# Shematic.net
KiCad netlist of a schematic drawn in Altium Designer
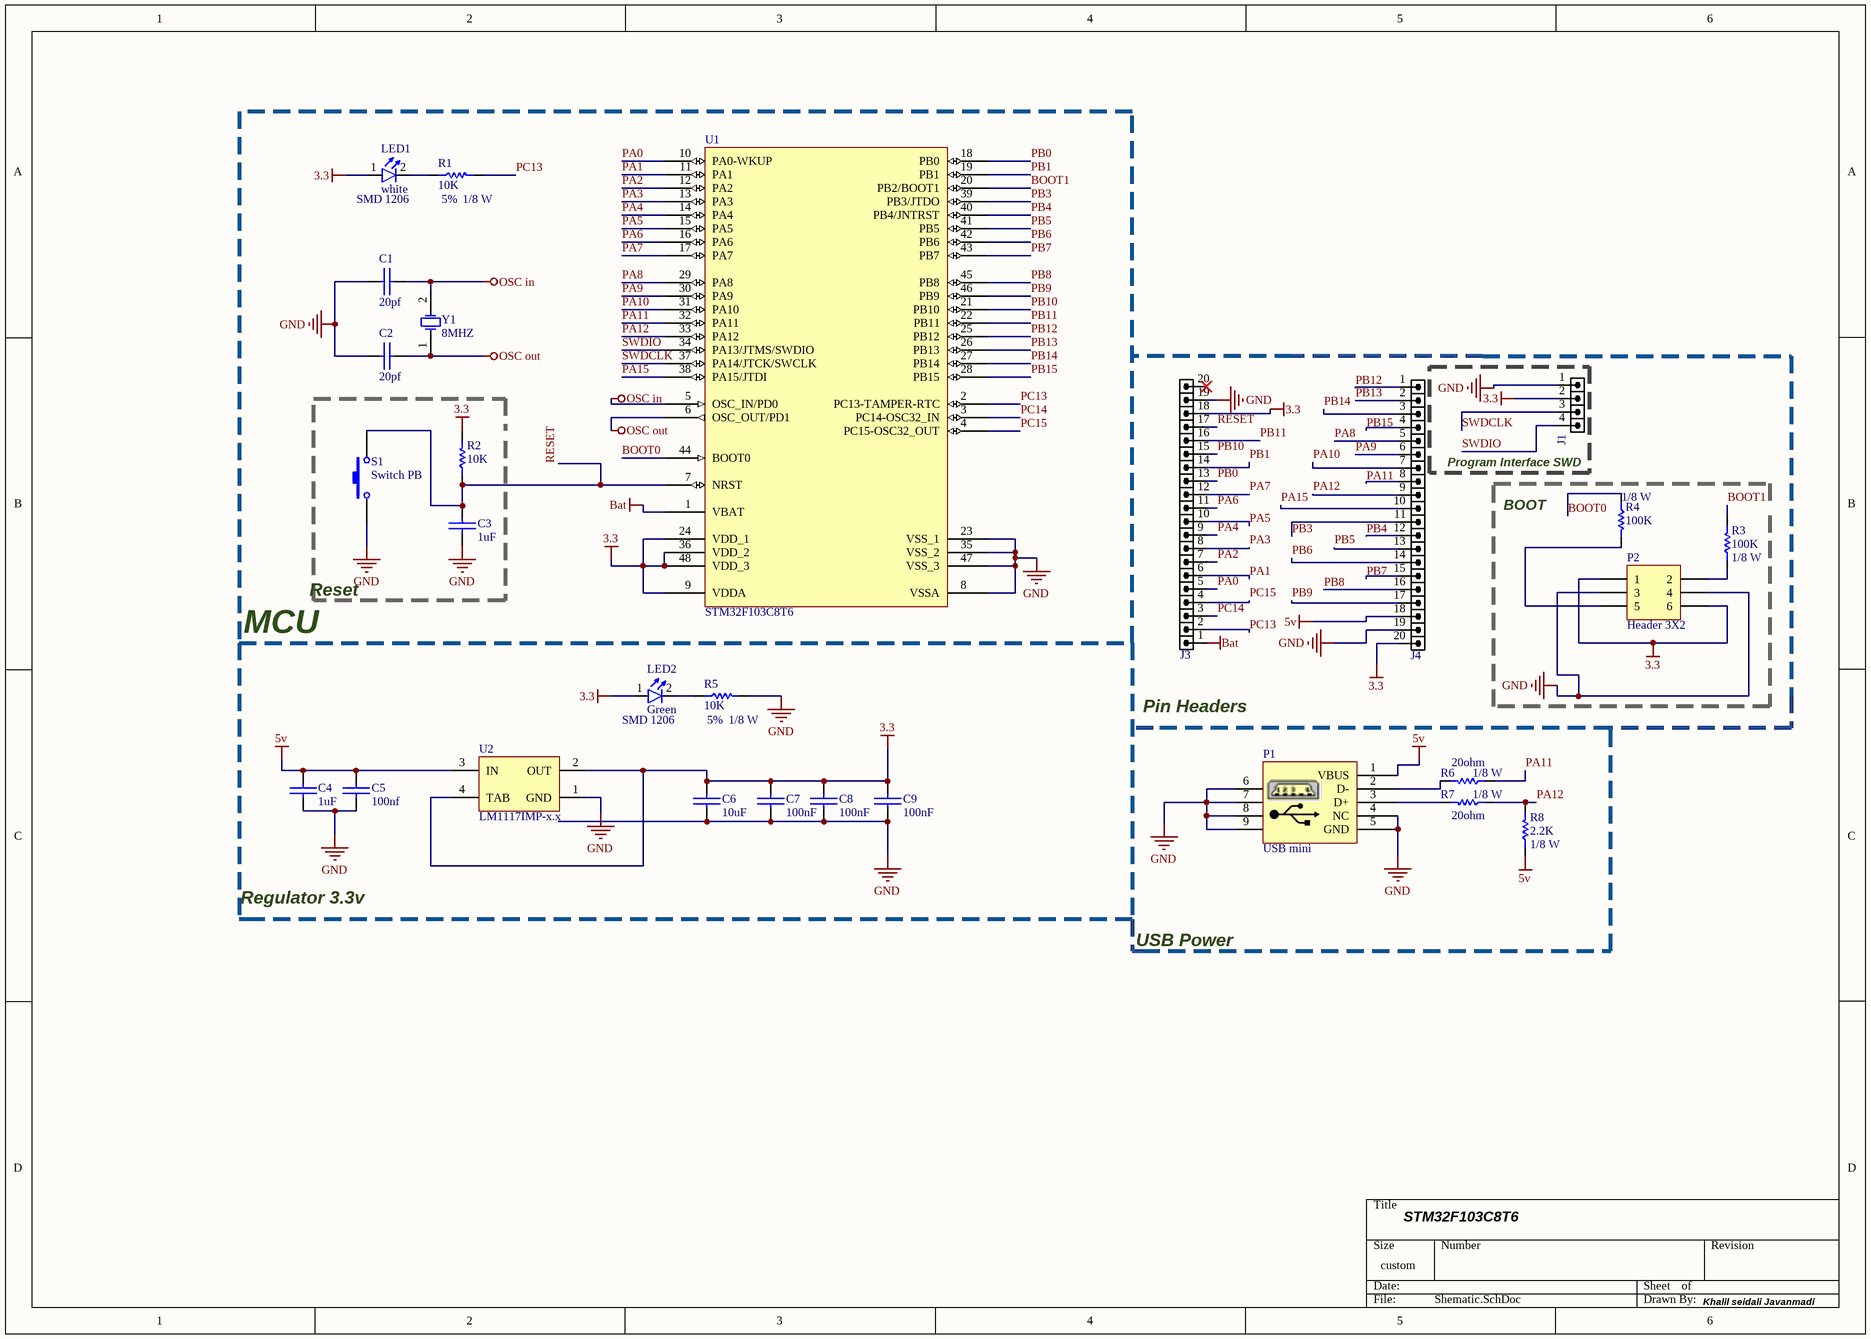
[diagram p0: Shematic.SchDoc]

(export (version "E")
  (design (tool "Eeschema 10.0.6"))
  (components
    (comp (ref "C1")
      (value "20pf")
      (footprint "SMD_CAP_0805")
      (description "Bipolar Capacitor")
      (fields (field (name "VOLTAGE") "100V") (field (name "DESIGNER") "Saeid Jorablo"))
      (libsource (lib "My_Library") (part "Cap-Bipolar"))
    )
    (comp (ref "C2")
      (value "20pf")
      (footprint "SMD_CAP_0805")
      (description "Bipolar Capacitor")
      (fields (field (name "VOLTAGE") "100V") (field (name "DESIGNER") "Saeid Jorablo"))
      (libsource (lib "My_Library") (part "Cap-Bipolar"))
    )
    (comp (ref "C3")
      (value "1uF")
      (footprint "SMD_CAP_0805")
      (description "Bipolar Capacitor")
      (fields (field (name "VOLTAGE") "100V") (field (name "DESIGNER") "Saeid Jorablo"))
      (libsource (lib "My_Library") (part "Cap-Bipolar"))
    )
    (comp (ref "C4")
      (value "1uF")
      (footprint "SMD_CAP_0805")
      (description "Bipolar Capacitor")
      (fields (field (name "VOLTAGE") "100V") (field (name "DESIGNER") "Saeid Jorablo"))
      (libsource (lib "My_Library") (part "Cap-Bipolar"))
    )
    (comp (ref "C5")
      (value "100nf")
      (footprint "SMD_CAP_0805")
      (description "Bipolar Capacitor")
      (fields (field (name "VOLTAGE") "100V") (field (name "DESIGNER") "Saeid Jorablo"))
      (libsource (lib "My_Library") (part "Cap-Bipolar"))
    )
    (comp (ref "C6")
      (value "10uF")
      (footprint "SMD_CAP_0805")
      (description "Bipolar Capacitor")
      (fields (field (name "VOLTAGE") "100V") (field (name "DESIGNER") "Saeid Jorablo"))
      (libsource (lib "My_Library") (part "Cap-Bipolar"))
    )
    (comp (ref "C7")
      (value "100nF")
      (footprint "SMD_CAP_0805")
      (description "Bipolar Capacitor")
      (fields (field (name "VOLTAGE") "100V") (field (name "DESIGNER") "Saeid Jorablo"))
      (libsource (lib "My_Library") (part "Cap-Bipolar"))
    )
    (comp (ref "C8")
      (value "100nF")
      (footprint "SMD_CAP_0805")
      (description "Bipolar Capacitor")
      (fields (field (name "VOLTAGE") "100V") (field (name "DESIGNER") "Saeid Jorablo"))
      (libsource (lib "My_Library") (part "Cap-Bipolar"))
    )
    (comp (ref "C9")
      (value "100nF")
      (footprint "SMD_CAP_0805")
      (description "Bipolar Capacitor")
      (fields (field (name "VOLTAGE") "100V") (field (name "DESIGNER") "Saeid Jorablo"))
      (libsource (lib "My_Library") (part "Cap-Bipolar"))
    )
    (comp (ref "J1")
      (value "HDR1X4")
      (footprint "HDR_M_1X4")
      (description "CONN, HEADER, Male, pitch: 2.54mm, 4POS")
      (libsource (lib "conn_header") (part "HDR_M_1X4"))
    )
    (comp (ref "J3")
      (value "HDR1X20")
      (footprint "HDR_M_1X20")
      (description "CONN, HEADER, Male, pitch: 2.54mm, 20POS")
      (libsource (lib "conn_header") (part "HDR_M_1X20"))
    )
    (comp (ref "J4")
      (value "HDR1X20")
      (footprint "HDR_M_1X20")
      (description "CONN, HEADER, Male, pitch: 2.54mm, 20POS")
      (libsource (lib "conn_header") (part "HDR_M_1X20"))
    )
    (comp (ref "LED1")
      (value "white")
      (footprint "LED SMD 1206")
      (description "LED")
      (fields
        (field (name "COLOR") "white")
        (field (name "SIZE") "SMD 1206")
        (field (name "DESIGNER") "Saeid Jorablo")
      )
      (libsource (lib "My_Library") (part "LED"))
    )
    (comp (ref "LED2")
      (value "Green")
      (footprint "LED SMD 1206")
      (description "LED")
      (fields
        (field (name "COLOR") "Green")
        (field (name "SIZE") "SMD 1206")
        (field (name "DESIGNER") "Saeid Jorablo")
      )
      (libsource (lib "My_Library") (part "LED"))
    )
    (comp (ref "P1")
      (value "USB mini")
      (footprint "SMD_Mini USB Connector")
      (description "mini USB Connector")
      (libsource (lib "My_Library") (part "USB mini"))
    )
    (comp (ref "P2")
      (value "Header 3X2")
      (footprint "HDR2X3")
      (description "Header, 3-Pin, Dual row")
      (fields (field (name "PUBLISHER") "Altium Limited"))
      (libsource (lib "Miscellaneous Connectors") (part "Header 3X2"))
    )
    (comp (ref "R1")
      (value "10K")
      (footprint "RES 0805 (2012X06L)")
      (description "Resistor")
      (fields (field (name "TOLERANCE") "5%") (field (name "POWER") "1/8 W"))
      (libsource (lib "My_Library") (part "Resistor"))
    )
    (comp (ref "R2")
      (value "10K")
      (footprint "RES 0805 (2012X06L)")
      (description "Resistor")
      (libsource (lib "My_Library") (part "Resistor"))
    )
    (comp (ref "R3")
      (value "100K")
      (footprint "RES 0805 (2012X06L)")
      (description "Resistor")
      (fields (field (name "POWER") "1/8 W"))
      (libsource (lib "My_Library") (part "Resistor"))
    )
    (comp (ref "R4")
      (value "100K")
      (footprint "RES 0805 (2012X06L)")
      (description "Resistor")
      (fields (field (name "POWER") "1/8 W"))
      (libsource (lib "My_Library") (part "Resistor"))
    )
    (comp (ref "R5")
      (value "10K")
      (footprint "RES 0805 (2012X06L)")
      (description "Resistor")
      (fields (field (name "TOLERANCE") "5%") (field (name "POWER") "1/8 W"))
      (libsource (lib "My_Library") (part "Resistor"))
    )
    (comp (ref "R6")
      (value "20ohm")
      (footprint "RES 0805 (2012X06L)")
      (description "Resistor")
      (fields (field (name "POWER") "1/8 W"))
      (libsource (lib "My_Library") (part "Resistor"))
    )
    (comp (ref "R7")
      (value "20ohm")
      (footprint "RES 0805 (2012X06L)")
      (description "Resistor")
      (fields (field (name "POWER") "1/8 W"))
      (libsource (lib "My_Library") (part "Resistor"))
    )
    (comp (ref "R8")
      (value "2.2K")
      (footprint "RES 0805 (2012X06L)")
      (description "Resistor")
      (fields (field (name "POWER") "1/8 W"))
      (libsource (lib "My_Library") (part "Resistor"))
    )
    (comp (ref "S1")
      (value "Switch PB")
      (footprint "SW-PB")
      (description "Push Button Switch")
      (libsource (lib "My_Library") (part "Switch PB"))
    )
    (comp (ref "U1")
      (value "STM32F103C8T6")
      (footprint "LQFP48_L")
      (description "STM32 ARM-based 32-bit MCU with 64 Kbytes Flash, 48-pin LQFP, Industrial Temperature")
      (fields (field (name "PUBLISHER") "Altium Limited"))
      (libsource (lib "ST Microcontroller 32-Bit STM32") (part "STM32F103C8T6"))
    )
    (comp (ref "U2")
      (value "LM1117IMP-x.x")
      (footprint "MP04A_N")
      (description "x.x Volt, 800mA Low-Dropout Linear Regulator, 4-pin SOT-223")
      (fields
        (field (name "PARTNUMBER") "LM1117IMP-3.3")
        (field (name "MANUFACTURER") "National Semiconductor")
        (field (name "PUBLISHER") "Altium Limited")
      )
      (libsource (lib "My_Library") (part "LM1117IMP-x.x"))
    )
    (comp (ref "Y1")
      (value "8MHZ")
      (footprint "Crystal SMD")
      (description "XTAL Crystal")
      (libsource (lib "My_Library") (part "XTAL"))
    )
  )
  (nets
    (net (code "1") (name "/BOOT0") (class "Default")
      (node (ref "R4") (pin "1") (pinfunction "1_1") (pintype "passive"))
      (node (ref "U1") (pin "44") (pinfunction "BOOT0_44") (pintype "input"))
    )
    (net (code "2") (name "/BOOT1") (class "Default")
      (node (ref "R3") (pin "2") (pinfunction "2_2") (pintype "passive"))
      (node (ref "U1") (pin "20") (pinfunction "PB2/BOOT1_20") (pintype "bidirectional"))
    )
    (net (code "3") (name "/PA0") (class "Default")
      (node (ref "J3") (pin "5") (pinfunction "5_5") (pintype "passive"))
      (node (ref "U1") (pin "10") (pinfunction "PA0-WKUP_10") (pintype "bidirectional"))
    )
    (net (code "4") (name "/PA1") (class "Default")
      (node (ref "J3") (pin "6") (pinfunction "6_6") (pintype "passive"))
      (node (ref "U1") (pin "11") (pinfunction "PA1_11") (pintype "bidirectional"))
    )
    (net (code "5") (name "/PA2") (class "Default")
      (node (ref "J3") (pin "7") (pinfunction "7_7") (pintype "passive"))
      (node (ref "U1") (pin "12") (pinfunction "PA2_12") (pintype "bidirectional"))
    )
    (net (code "6") (name "/PA3") (class "Default")
      (node (ref "J3") (pin "8") (pinfunction "8_8") (pintype "passive"))
      (node (ref "U1") (pin "13") (pinfunction "PA3_13") (pintype "bidirectional"))
    )
    (net (code "7") (name "/PA4") (class "Default")
      (node (ref "J3") (pin "9") (pinfunction "9_9") (pintype "passive"))
      (node (ref "U1") (pin "14") (pinfunction "PA4_14") (pintype "bidirectional"))
    )
    (net (code "8") (name "/PA5") (class "Default")
      (node (ref "J3") (pin "10") (pinfunction "10_10") (pintype "passive"))
      (node (ref "U1") (pin "15") (pinfunction "PA5_15") (pintype "bidirectional"))
    )
    (net (code "9") (name "/PA6") (class "Default")
      (node (ref "J3") (pin "11") (pinfunction "11_11") (pintype "passive"))
      (node (ref "U1") (pin "16") (pinfunction "PA6_16") (pintype "bidirectional"))
    )
    (net (code "10") (name "/PA7") (class "Default")
      (node (ref "J3") (pin "12") (pinfunction "12_12") (pintype "passive"))
      (node (ref "U1") (pin "17") (pinfunction "PA7_17") (pintype "bidirectional"))
    )
    (net (code "11") (name "/PA8") (class "Default")
      (node (ref "J4") (pin "5") (pinfunction "5_5") (pintype "passive"))
      (node (ref "U1") (pin "29") (pinfunction "PA8_29") (pintype "bidirectional"))
    )
    (net (code "12") (name "/PA9") (class "Default")
      (node (ref "J4") (pin "6") (pinfunction "6_6") (pintype "passive"))
      (node (ref "U1") (pin "30") (pinfunction "PA9_30") (pintype "bidirectional"))
    )
    (net (code "13") (name "/PA10") (class "Default")
      (node (ref "J4") (pin "7") (pinfunction "7_7") (pintype "passive"))
      (node (ref "U1") (pin "31") (pinfunction "PA10_31") (pintype "bidirectional"))
    )
    (net (code "14") (name "/PA11") (class "Default")
      (node (ref "J4") (pin "8") (pinfunction "8_8") (pintype "passive"))
      (node (ref "R6") (pin "1") (pinfunction "1_1") (pintype "passive"))
      (node (ref "U1") (pin "32") (pinfunction "PA11_32") (pintype "bidirectional"))
    )
    (net (code "15") (name "/PA12") (class "Default")
      (node (ref "J4") (pin "9") (pinfunction "9_9") (pintype "passive"))
      (node (ref "R7") (pin "1") (pinfunction "1_1") (pintype "passive"))
      (node (ref "R8") (pin "2") (pinfunction "2_2") (pintype "passive"))
      (node (ref "U1") (pin "33") (pinfunction "PA12_33") (pintype "bidirectional"))
    )
    (net (code "16") (name "/PA15") (class "Default")
      (node (ref "J4") (pin "10") (pinfunction "10_10") (pintype "passive"))
      (node (ref "U1") (pin "38") (pinfunction "PA15/JTDI_38") (pintype "bidirectional"))
    )
    (net (code "17") (name "/PB0") (class "Default")
      (node (ref "J3") (pin "13") (pinfunction "13_13") (pintype "passive"))
      (node (ref "U1") (pin "18") (pinfunction "PB0_18") (pintype "bidirectional"))
    )
    (net (code "18") (name "/PB1") (class "Default")
      (node (ref "J3") (pin "14") (pinfunction "14_14") (pintype "passive"))
      (node (ref "U1") (pin "19") (pinfunction "PB1_19") (pintype "bidirectional"))
    )
    (net (code "19") (name "/PB3") (class "Default")
      (node (ref "J4") (pin "11") (pinfunction "11_11") (pintype "passive"))
      (node (ref "U1") (pin "39") (pinfunction "PB3/JTDO_39") (pintype "bidirectional"))
    )
    (net (code "20") (name "/PB4") (class "Default")
      (node (ref "J4") (pin "12") (pinfunction "12_12") (pintype "passive"))
      (node (ref "U1") (pin "40") (pinfunction "PB4/JNTRST_40") (pintype "bidirectional"))
    )
    (net (code "21") (name "/PB5") (class "Default")
      (node (ref "J4") (pin "13") (pinfunction "13_13") (pintype "passive"))
      (node (ref "U1") (pin "41") (pinfunction "PB5_41") (pintype "bidirectional"))
    )
    (net (code "22") (name "/PB6") (class "Default")
      (node (ref "J4") (pin "14") (pinfunction "14_14") (pintype "passive"))
      (node (ref "U1") (pin "42") (pinfunction "PB6_42") (pintype "bidirectional"))
    )
    (net (code "23") (name "/PB7") (class "Default")
      (node (ref "J4") (pin "15") (pinfunction "15_15") (pintype "passive"))
      (node (ref "U1") (pin "43") (pinfunction "PB7_43") (pintype "bidirectional"))
    )
    (net (code "24") (name "/PB8") (class "Default")
      (node (ref "J4") (pin "16") (pinfunction "16_16") (pintype "passive"))
      (node (ref "U1") (pin "45") (pinfunction "PB8_45") (pintype "bidirectional"))
    )
    (net (code "25") (name "/PB9") (class "Default")
      (node (ref "J4") (pin "17") (pinfunction "17_17") (pintype "passive"))
      (node (ref "U1") (pin "46") (pinfunction "PB9_46") (pintype "bidirectional"))
    )
    (net (code "26") (name "/PB10") (class "Default")
      (node (ref "J3") (pin "15") (pinfunction "15_15") (pintype "passive"))
      (node (ref "U1") (pin "21") (pinfunction "PB10_21") (pintype "bidirectional"))
    )
    (net (code "27") (name "/PB11") (class "Default")
      (node (ref "J3") (pin "16") (pinfunction "16_16") (pintype "passive"))
      (node (ref "U1") (pin "22") (pinfunction "PB11_22") (pintype "bidirectional"))
    )
    (net (code "28") (name "/PB12") (class "Default")
      (node (ref "J4") (pin "1") (pinfunction "1_1") (pintype "passive"))
      (node (ref "U1") (pin "25") (pinfunction "PB12_25") (pintype "bidirectional"))
    )
    (net (code "29") (name "/PB13") (class "Default")
      (node (ref "J4") (pin "2") (pinfunction "2_2") (pintype "passive"))
      (node (ref "U1") (pin "26") (pinfunction "PB13_26") (pintype "bidirectional"))
    )
    (net (code "30") (name "/PB14") (class "Default")
      (node (ref "J4") (pin "3") (pinfunction "3_3") (pintype "passive"))
      (node (ref "U1") (pin "27") (pinfunction "PB14_27") (pintype "bidirectional"))
    )
    (net (code "31") (name "/PB15") (class "Default")
      (node (ref "J4") (pin "4") (pinfunction "4_4") (pintype "passive"))
      (node (ref "U1") (pin "28") (pinfunction "PB15_28") (pintype "bidirectional"))
    )
    (net (code "32") (name "/PC13") (class "Default")
      (node (ref "J3") (pin "2") (pinfunction "2_2") (pintype "passive"))
      (node (ref "R1") (pin "2") (pinfunction "2_2") (pintype "passive"))
      (node (ref "U1") (pin "2") (pinfunction "PC13-TAMPER-RTC_2") (pintype "bidirectional"))
    )
    (net (code "33") (name "/PC14") (class "Default")
      (node (ref "J3") (pin "3") (pinfunction "3_3") (pintype "passive"))
      (node (ref "U1") (pin "3") (pinfunction "PC14-OSC32_IN_3") (pintype "bidirectional"))
    )
    (net (code "34") (name "/PC15") (class "Default")
      (node (ref "J3") (pin "4") (pinfunction "4_4") (pintype "passive"))
      (node (ref "U1") (pin "4") (pinfunction "PC15-OSC32_OUT_4") (pintype "bidirectional"))
    )
    (net (code "35") (name "/RESET") (class "Default")
      (node (ref "C3") (pin "1") (pinfunction "+_1") (pintype "passive"))
      (node (ref "J3") (pin "17") (pinfunction "17_17") (pintype "passive"))
      (node (ref "R2") (pin "1") (pinfunction "1_1") (pintype "passive"))
      (node (ref "S1") (pin "2") (pinfunction "2_2") (pintype "passive"))
      (node (ref "U1") (pin "7") (pinfunction "NRST_7") (pintype "bidirectional"))
    )
    (net (code "36") (name "/SWDCLK") (class "Default")
      (node (ref "J1") (pin "3") (pinfunction "3_3") (pintype "passive"))
      (node (ref "U1") (pin "37") (pinfunction "PA14/JTCK/SWCLK_37") (pintype "bidirectional"))
    )
    (net (code "37") (name "/SWDIO") (class "Default")
      (node (ref "J1") (pin "4") (pinfunction "4_4") (pintype "passive"))
      (node (ref "U1") (pin "34") (pinfunction "PA13/JTMS/SWDIO_34") (pintype "bidirectional"))
    )
    (net (code "38") (name "3.3") (class "Default")
      (node (ref "C6") (pin "1") (pinfunction "+_1") (pintype "passive"))
      (node (ref "C7") (pin "1") (pinfunction "+_1") (pintype "passive"))
      (node (ref "C8") (pin "1") (pinfunction "+_1") (pintype "passive"))
      (node (ref "C9") (pin "1") (pinfunction "+_1") (pintype "passive"))
      (node (ref "J1") (pin "2") (pinfunction "2_2") (pintype "passive"))
      (node (ref "J3") (pin "18") (pinfunction "18_18") (pintype "passive"))
      (node (ref "J4") (pin "20") (pinfunction "20_20") (pintype "passive"))
      (node (ref "LED1") (pin "1") (pinfunction "A_1") (pintype "passive"))
      (node (ref "LED2") (pin "1") (pinfunction "A_1") (pintype "passive"))
      (node (ref "P2") (pin "1") (pinfunction "1_1") (pintype "passive"))
      (node (ref "P2") (pin "6") (pinfunction "6_6") (pintype "passive"))
      (node (ref "R2") (pin "2") (pinfunction "2_2") (pintype "passive"))
      (node (ref "U1") (pin "24") (pinfunction "VDD_1_24") (pintype "power_in"))
      (node (ref "U1") (pin "36") (pinfunction "VDD_2_36") (pintype "power_in"))
      (node (ref "U1") (pin "48") (pinfunction "VDD_3_48") (pintype "power_in"))
      (node (ref "U1") (pin "9") (pinfunction "VDDA_9") (pintype "power_in"))
      (node (ref "U2") (pin "2") (pinfunction "OUT_2") (pintype "power_in"))
      (node (ref "U2") (pin "4") (pinfunction "TAB_4") (pintype "power_in"))
    )
    (net (code "39") (name "5v") (class "Default")
      (node (ref "C4") (pin "1") (pinfunction "+_1") (pintype "passive"))
      (node (ref "C5") (pin "1") (pinfunction "+_1") (pintype "passive"))
      (node (ref "J4") (pin "18") (pinfunction "18_18") (pintype "passive"))
      (node (ref "P1") (pin "1") (pinfunction "VBUS_1") (pintype "power_in"))
      (node (ref "R8") (pin "1") (pinfunction "1_1") (pintype "passive"))
      (node (ref "U2") (pin "3") (pinfunction "IN_3") (pintype "power_in"))
    )
    (net (code "40") (name "Bat") (class "Default")
      (node (ref "J3") (pin "1") (pinfunction "1_1") (pintype "passive"))
      (node (ref "U1") (pin "1") (pinfunction "VBAT_1") (pintype "power_in"))
    )
    (net (code "41") (name "GND") (class "Default")
      (node (ref "C1") (pin "1") (pinfunction "+_1") (pintype "passive"))
      (node (ref "C2") (pin "1") (pinfunction "+_1") (pintype "passive"))
      (node (ref "C3") (pin "2") (pinfunction "-_2") (pintype "passive"))
      (node (ref "C4") (pin "2") (pinfunction "-_2") (pintype "passive"))
      (node (ref "C5") (pin "2") (pinfunction "-_2") (pintype "passive"))
      (node (ref "C6") (pin "2") (pinfunction "-_2") (pintype "passive"))
      (node (ref "C7") (pin "2") (pinfunction "-_2") (pintype "passive"))
      (node (ref "C8") (pin "2") (pinfunction "-_2") (pintype "passive"))
      (node (ref "C9") (pin "2") (pinfunction "-_2") (pintype "passive"))
      (node (ref "J1") (pin "1") (pinfunction "1_1") (pintype "passive"))
      (node (ref "J3") (pin "19") (pinfunction "19_19") (pintype "passive"))
      (node (ref "J4") (pin "19") (pinfunction "19_19") (pintype "passive"))
      (node (ref "P1") (pin "4") (pinfunction "NC_4") (pintype "power_in"))
      (node (ref "P1") (pin "5") (pinfunction "GND_5") (pintype "power_in"))
      (node (ref "P1") (pin "6") (pinfunction "6_6") (pintype "passive"))
      (node (ref "P1") (pin "7") (pinfunction "7_7") (pintype "passive"))
      (node (ref "P1") (pin "8") (pinfunction "8_8") (pintype "passive"))
      (node (ref "P1") (pin "9") (pinfunction "9_9") (pintype "passive"))
      (node (ref "P2") (pin "3") (pinfunction "3_3") (pintype "passive"))
      (node (ref "P2") (pin "4") (pinfunction "4_4") (pintype "passive"))
      (node (ref "R5") (pin "2") (pinfunction "2_2") (pintype "passive"))
      (node (ref "S1") (pin "1") (pinfunction "1_1") (pintype "passive"))
      (node (ref "U1") (pin "23") (pinfunction "VSS_1_23") (pintype "power_in"))
      (node (ref "U1") (pin "35") (pinfunction "VSS_2_35") (pintype "power_in"))
      (node (ref "U1") (pin "47") (pinfunction "VSS_3_47") (pintype "power_in"))
      (node (ref "U1") (pin "8") (pinfunction "VSSA_8") (pintype "power_in"))
      (node (ref "U2") (pin "1") (pinfunction "GND_1") (pintype "power_in"))
    )
    (net (code "42") (name "Net-(LED1-K)") (class "Default")
      (node (ref "LED1") (pin "2") (pinfunction "K_2") (pintype "passive"))
      (node (ref "R1") (pin "1") (pinfunction "1_1") (pintype "passive"))
    )
    (net (code "43") (name "Net-(LED2-K)") (class "Default")
      (node (ref "LED2") (pin "2") (pinfunction "K_2") (pintype "passive"))
      (node (ref "R5") (pin "1") (pinfunction "1_1") (pintype "passive"))
    )
    (net (code "44") (name "Net-(P1-D+)") (class "Default")
      (node (ref "P1") (pin "3") (pinfunction "D+_3") (pintype "passive"))
      (node (ref "R7") (pin "2") (pinfunction "2_2") (pintype "passive"))
    )
    (net (code "45") (name "Net-(P1-D-)") (class "Default")
      (node (ref "P1") (pin "2") (pinfunction "D-_2") (pintype "passive"))
      (node (ref "R6") (pin "2") (pinfunction "2_2") (pintype "passive"))
    )
    (net (code "46") (name "Net-(P2-Pad2)") (class "Default")
      (node (ref "P2") (pin "2") (pinfunction "2_2") (pintype "passive"))
      (node (ref "R3") (pin "1") (pinfunction "1_1") (pintype "passive"))
    )
    (net (code "47") (name "Net-(P2-Pad5)") (class "Default")
      (node (ref "P2") (pin "5") (pinfunction "5_5") (pintype "passive"))
      (node (ref "R4") (pin "2") (pinfunction "2_2") (pintype "passive"))
    )
    (net (code "48") (name "OSC in") (class "Default")
      (node (ref "C1") (pin "2") (pinfunction "-_2") (pintype "passive"))
      (node (ref "U1") (pin "5") (pinfunction "OSC_IN/PD0_5") (pintype "input"))
      (node (ref "Y1") (pin "2") (pinfunction "OSC2_2") (pintype "passive"))
    )
    (net (code "49") (name "OSC out") (class "Default")
      (node (ref "C2") (pin "2") (pinfunction "-_2") (pintype "passive"))
      (node (ref "U1") (pin "6") (pinfunction "OSC_OUT/PD1_6") (pintype "output"))
      (node (ref "Y1") (pin "1") (pinfunction "OSC1_1") (pintype "passive"))
    )
    (net (code "50") (name "unconnected-(J3-Pad20)") (class "Default")
      (node (ref "J3") (pin "20") (pinfunction "20_20") (pintype "passive+no_connect"))
    )
  )
)
